# design.net
KiCad netlist of a schematic drawn in Altium Designer
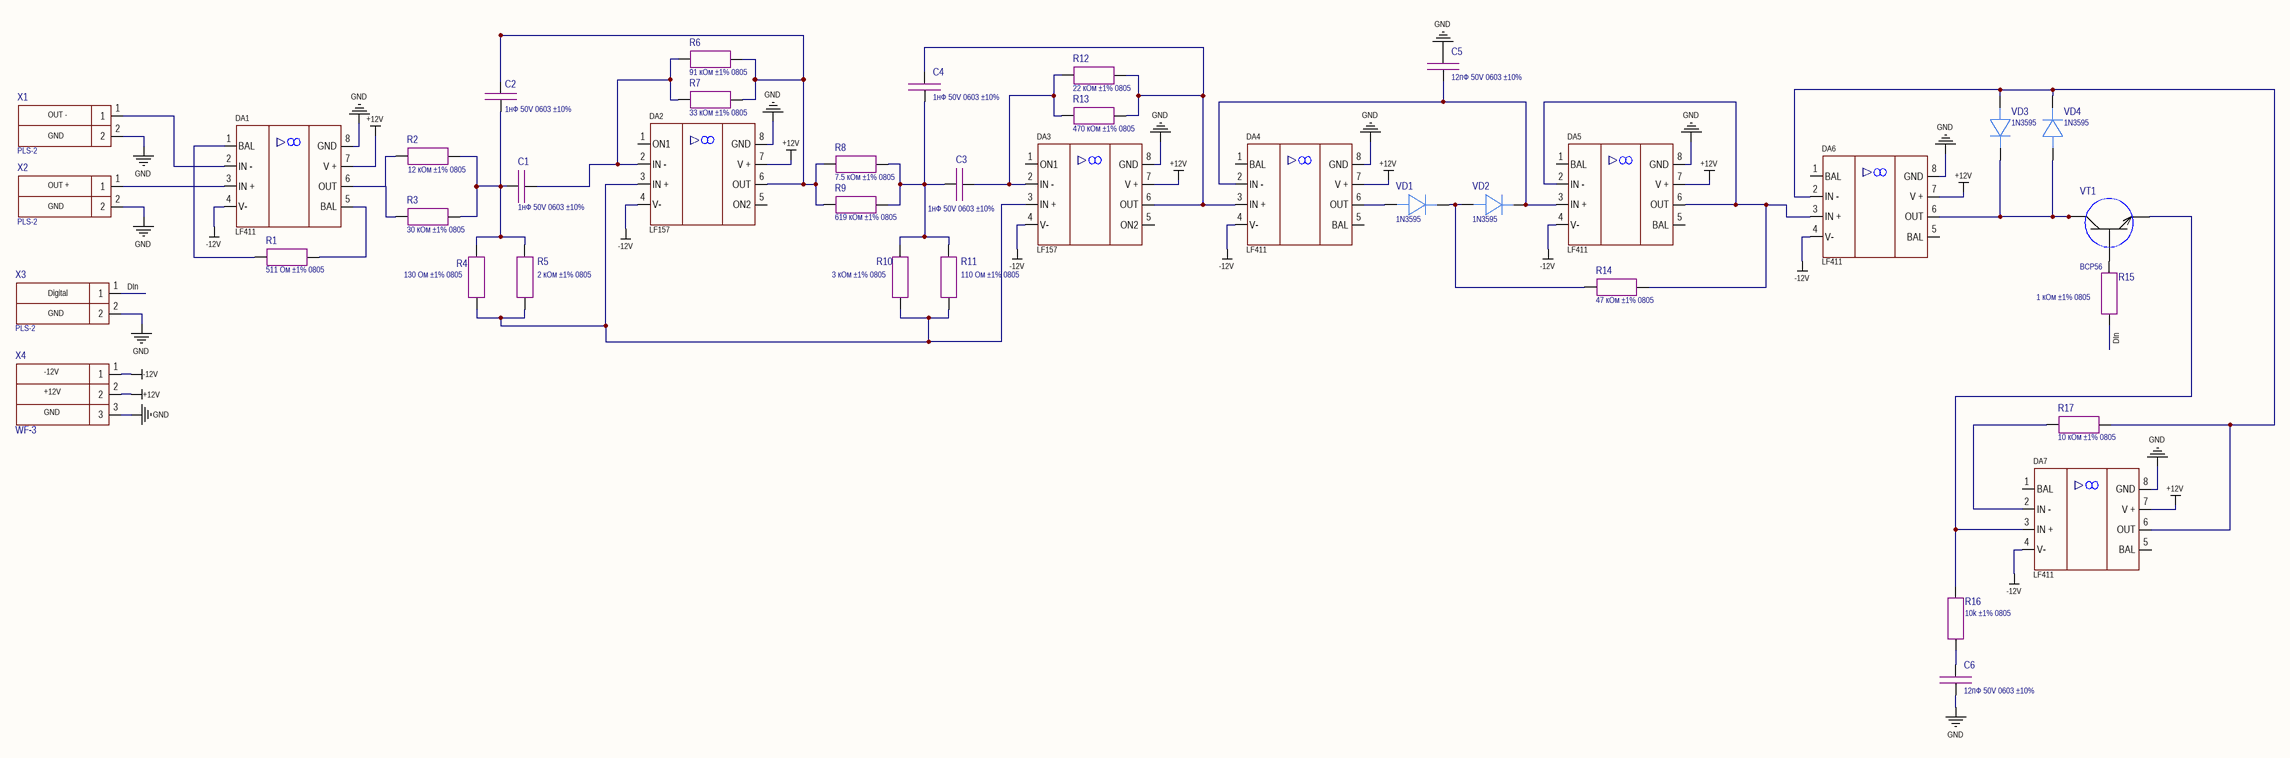
[diagram p0: ДЗ.SchDoc]

(export (version "E")
  (design (tool "Eeschema 10.0.6"))
  (components
    (comp (ref "C1")
      (value "1нФ 50V 0603 ±10%")
      (footprint "CAP: SMD 0603 MD IPC 782")
      (libsource (lib "UOMP capacitors") (part "47p 50V 0603 ±10%"))
    )
    (comp (ref "C2")
      (value "1нФ 50V 0603 ±10%")
      (footprint "CAP: SMD 0603 MD IPC 782")
      (libsource (lib "UOMP capacitors") (part "47p 50V 0603 ±10%"))
    )
    (comp (ref "C3")
      (value "1нФ 50V 0603 ±10%")
      (footprint "CAP: SMD 0603 MD IPC 782")
      (libsource (lib "UOMP capacitors") (part "47p 50V 0603 ±10%"))
    )
    (comp (ref "C4")
      (value "1нФ 50V 0603 ±10%")
      (footprint "CAP: SMD 0603 MD IPC 782")
      (libsource (lib "UOMP capacitors") (part "47p 50V 0603 ±10%"))
    )
    (comp (ref "C5")
      (value "12пФ 50V 0603 ±10%")
      (footprint "CAP: SMD 0603 MD IPC 782")
      (libsource (lib "UOMP capacitors") (part "47p 50V 0603 ±10%"))
    )
    (comp (ref "C6")
      (value "12пФ 50V 0603 ±10%")
      (footprint "CAP: SMD 0603 MD IPC 782")
      (libsource (lib "UOMP capacitors") (part "47p 50V 0603 ±10%"))
    )
    (comp (ref "DA1") (value "LF411") (footprint "IC: PDIP-8") (libsource (lib "") (part "LF411_1")))
    (comp (ref "DA2")
      (value "LF157")
      (footprint "IC: SOIC 8")
      (libsource (lib "UOMP operational amplifier") (part "LF157"))
    )
    (comp (ref "DA3")
      (value "LF157")
      (footprint "IC: SOIC 8")
      (libsource (lib "UOMP operational amplifier") (part "LF157"))
    )
    (comp (ref "DA4") (value "LF411") (footprint "IC: PDIP-8") (libsource (lib "") (part "LF411_1")))
    (comp (ref "DA5")
      (value "LF411")
      (footprint "IC: PDIP-8")
      (libsource (lib "UOMP operational amplifier") (part "LF411"))
    )
    (comp (ref "DA6")
      (value "LF411")
      (footprint "IC: PDIP-8")
      (libsource (lib "UOMP operational amplifier") (part "LF411"))
    )
    (comp (ref "DA7") (value "LF411") (footprint "IC: PDIP-8") (libsource (lib "") (part "LF411_1")))
    (comp (ref "R1")
      (value "511 Ом ±1% 0805")
      (footprint "RES: SMD 0805 MD IPC 782")
      (libsource (lib "UOMP resistors") (part "510 ±1% 0805"))
    )
    (comp (ref "R2")
      (value "12 кОм ±1% 0805")
      (footprint "RES: SMD 0805 MD IPC 782")
      (libsource (lib "UOMP resistors") (part "15k ±1% 0805"))
    )
    (comp (ref "R3")
      (value "30 кОм ±1% 0805")
      (footprint "RES: SMD 0805 MD IPC 782")
      (libsource (lib "UOMP resistors") (part "20k ±1% 0805"))
    )
    (comp (ref "R4")
      (value "130 Ом ±1% 0805")
      (footprint "RES: SMD 0805 MD IPC 782")
      (libsource (lib "UOMP resistors") (part "100k ±1% 0805"))
    )
    (comp (ref "R5")
      (value "2 кОм ±1% 0805")
      (footprint "RES: SMD 0805 MD IPC 782")
      (libsource (lib "UOMP resistors") (part "100k ±1% 0805"))
    )
    (comp (ref "R6")
      (value "91 кОм ±1% 0805")
      (footprint "RES: SMD 0805 MD IPC 782")
      (libsource (lib "UOMP resistors") (part "2k ±1% 0805"))
    )
    (comp (ref "R7")
      (value "33 кОм ±1% 0805")
      (footprint "RES: SMD 0805 MD IPC 782")
      (libsource (lib "UOMP resistors") (part "2k ±1% 0805"))
    )
    (comp (ref "R8")
      (value "7.5 кОм ±1% 0805")
      (footprint "RES: SMD 0805 MD IPC 782")
      (libsource (lib "UOMP resistors") (part "2k ±1% 0805"))
    )
    (comp (ref "R9")
      (value "619 кОм ±1% 0805")
      (footprint "RES: SMD 0805 MD IPC 782")
      (libsource (lib "UOMP resistors") (part "2k ±1% 0805"))
    )
    (comp (ref "R10")
      (value "3 кОм ±1% 0805")
      (footprint "RES: SMD 0805 MD IPC 782")
      (libsource (lib "UOMP resistors") (part "100k ±1% 0805"))
    )
    (comp (ref "R11")
      (value "110 Ом ±1% 0805")
      (footprint "RES: SMD 0805 MD IPC 782")
      (libsource (lib "UOMP resistors") (part "100k ±1% 0805"))
    )
    (comp (ref "R12")
      (value "22 кОм ±1% 0805")
      (footprint "RES: SMD 0805 MD IPC 782")
      (libsource (lib "UOMP resistors") (part "2k ±1% 0805"))
    )
    (comp (ref "R13")
      (value "470 кОм ±1% 0805")
      (footprint "RES: SMD 0805 MD IPC 782")
      (libsource (lib "UOMP resistors") (part "2k ±1% 0805"))
    )
    (comp (ref "R14")
      (value "47 кОм ±1% 0805")
      (footprint "RES: SMD 0805 MD IPC 782")
      (libsource (lib "UOMP resistors") (part "2k ±1% 0805"))
    )
    (comp (ref "R15")
      (value "1 кОм ±1% 0805")
      (footprint "RES: SMD 0805 MD IPC 782")
      (libsource (lib "UOMP resistors") (part "2k ±1% 0805"))
    )
    (comp (ref "R16")
      (value "10k ±1% 0805")
      (footprint "RES: SMD 0805 MD IPC 782")
      (libsource (lib "UOMP resistors") (part "10k ±1% 0805"))
    )
    (comp (ref "R17")
      (value "10 кОм ±1% 0805")
      (footprint "RES: SMD 0805 MD IPC 782")
      (libsource (lib "UOMP resistors") (part "2k ±1% 0805"))
    )
    (comp (ref "VD1")
      (value "1N3595")
      (footprint "DIODE: SMB")
      (libsource (lib "UOMP diode") (part "Rectifier 1A 40V"))
    )
    (comp (ref "VD2")
      (value "1N3595")
      (footprint "DIODE: SMB")
      (libsource (lib "UOMP diode") (part "Rectifier 1A 40V"))
    )
    (comp (ref "VD3")
      (value "1N3595")
      (footprint "DIODE: SMB")
      (libsource (lib "UOMP diode") (part "Rectifier 1A 40V"))
    )
    (comp (ref "VD4")
      (value "1N3595")
      (footprint "DIODE: SMB")
      (libsource (lib "UOMP diode") (part "Rectifier 1A 40V"))
    )
    (comp (ref "VT1")
      (value "BCP56")
      (footprint "IC: SOT 223")
      (libsource (lib "UOMP transistors") (part "BJT NPN BCP56"))
    )
    (comp (ref "X1")
      (value "PLS-2")
      (footprint "CON: 2PIN PLS 2")
      (libsource (lib "UOMP connectors") (part "2 pin PLS 2"))
    )
    (comp (ref "X2")
      (value "PLS-2")
      (footprint "CON: 2PIN PLS 2")
      (libsource (lib "UOMP connectors") (part "2 pin PLS 2"))
    )
    (comp (ref "X3")
      (value "PLS-2")
      (footprint "CON: 2PIN PLS 2")
      (libsource (lib "UOMP connectors") (part "2 pin PLS 2"))
    )
    (comp (ref "X4")
      (value "WF-3")
      (footprint "CON: 3pin wf-3")
      (libsource (lib "UOMP connectors") (part "3 pin WF-3"))
    )
  )
  (nets
    (net (code "1") (name "+12V") (class "Default")
      (node (ref "DA1") (pin "7") (pinfunction "V_+_7") (pintype "passive"))
      (node (ref "DA2") (pin "7") (pinfunction "V_+_7") (pintype "passive"))
      (node (ref "DA3") (pin "7") (pinfunction "V_+_7") (pintype "passive"))
      (node (ref "DA4") (pin "7") (pinfunction "V_+_7") (pintype "passive"))
      (node (ref "DA5") (pin "7") (pinfunction "V_+_7") (pintype "passive"))
      (node (ref "DA6") (pin "7") (pinfunction "V_+_7") (pintype "passive"))
      (node (ref "DA7") (pin "7") (pinfunction "V_+_7") (pintype "passive"))
      (node (ref "X4") (pin "2") (pinfunction "2_2") (pintype "passive"))
    )
    (net (code "2") (name "-12V") (class "Default")
      (node (ref "DA1") (pin "4") (pinfunction "V-_4") (pintype "passive"))
      (node (ref "DA2") (pin "4") (pinfunction "V-_4") (pintype "passive"))
      (node (ref "DA3") (pin "4") (pinfunction "V-_4") (pintype "passive"))
      (node (ref "DA4") (pin "4") (pinfunction "V-_4") (pintype "passive"))
      (node (ref "DA5") (pin "4") (pinfunction "V-_4") (pintype "passive"))
      (node (ref "DA6") (pin "4") (pinfunction "V-_4") (pintype "passive"))
      (node (ref "DA7") (pin "4") (pinfunction "V-_4") (pintype "passive"))
      (node (ref "X4") (pin "1") (pinfunction "1_1") (pintype "passive"))
    )
    (net (code "3") (name "/DIn") (class "Default")
      (node (ref "R15") (pin "2") (pinfunction "2_2") (pintype "passive"))
      (node (ref "X3") (pin "1") (pinfunction "1_1") (pintype "passive"))
    )
    (net (code "4") (name "GND") (class "Default")
      (node (ref "C5") (pin "2") (pinfunction "2_2") (pintype "passive"))
      (node (ref "C6") (pin "1") (pinfunction "1_1") (pintype "passive"))
      (node (ref "DA1") (pin "8") (pinfunction "GND_8") (pintype "passive"))
      (node (ref "DA2") (pin "8") (pinfunction "GND_8") (pintype "passive"))
      (node (ref "DA3") (pin "8") (pinfunction "GND_8") (pintype "passive"))
      (node (ref "DA4") (pin "8") (pinfunction "GND_8") (pintype "passive"))
      (node (ref "DA5") (pin "8") (pinfunction "GND_8") (pintype "passive"))
      (node (ref "DA6") (pin "8") (pinfunction "GND_8") (pintype "passive"))
      (node (ref "DA7") (pin "8") (pinfunction "GND_8") (pintype "passive"))
      (node (ref "X1") (pin "2") (pinfunction "2_2") (pintype "passive"))
      (node (ref "X2") (pin "2") (pinfunction "2_2") (pintype "passive"))
      (node (ref "X3") (pin "2") (pinfunction "2_2") (pintype "passive"))
      (node (ref "X4") (pin "3") (pinfunction "3_3") (pintype "passive"))
    )
    (net (code "5") (name "Net-(C1-Pad2)") (class "Default")
      (node (ref "C1") (pin "2") (pinfunction "2_2") (pintype "passive"))
      (node (ref "C2") (pin "2") (pinfunction "2_2") (pintype "passive"))
      (node (ref "R2") (pin "2") (pinfunction "2_2") (pintype "passive"))
      (node (ref "R3") (pin "2") (pinfunction "2_2") (pintype "passive"))
      (node (ref "R4") (pin "2") (pinfunction "2_2") (pintype "passive"))
      (node (ref "R5") (pin "2") (pinfunction "2_2") (pintype "passive"))
    )
    (net (code "6") (name "Net-(C3-Pad2)") (class "Default")
      (node (ref "C3") (pin "2") (pinfunction "2_2") (pintype "passive"))
      (node (ref "C4") (pin "1") (pinfunction "1_1") (pintype "passive"))
      (node (ref "R10") (pin "2") (pinfunction "2_2") (pintype "passive"))
      (node (ref "R11") (pin "2") (pinfunction "2_2") (pintype "passive"))
      (node (ref "R8") (pin "2") (pinfunction "2_2") (pintype "passive"))
      (node (ref "R9") (pin "2") (pinfunction "2_2") (pintype "passive"))
    )
    (net (code "7") (name "Net-(C6-Pad2)") (class "Default")
      (node (ref "C6") (pin "2") (pinfunction "2_2") (pintype "passive"))
      (node (ref "R16") (pin "2") (pinfunction "2_2") (pintype "passive"))
    )
    (net (code "8") (name "Net-(DA1-BAL-Pad1)") (class "Default")
      (node (ref "DA1") (pin "1") (pinfunction "BAL_1") (pintype "passive"))
      (node (ref "R1") (pin "1") (pinfunction "1_1") (pintype "passive"))
    )
    (net (code "9") (name "Net-(DA1-BAL-Pad5)") (class "Default")
      (node (ref "DA1") (pin "5") (pinfunction "BAL_5") (pintype "passive"))
      (node (ref "R1") (pin "2") (pinfunction "2_2") (pintype "passive"))
    )
    (net (code "10") (name "Net-(DA1-IN_+)") (class "Default")
      (node (ref "DA1") (pin "3") (pinfunction "IN_+_3") (pintype "passive"))
      (node (ref "X2") (pin "1") (pinfunction "1_1") (pintype "passive"))
    )
    (net (code "11") (name "Net-(DA1-IN_-)") (class "Default")
      (node (ref "DA1") (pin "2") (pinfunction "IN_-_2") (pintype "passive"))
      (node (ref "X1") (pin "1") (pinfunction "1_1") (pintype "passive"))
    )
    (net (code "12") (name "Net-(DA1-OUT)") (class "Default")
      (node (ref "DA1") (pin "6") (pinfunction "OUT_6") (pintype "passive"))
      (node (ref "R2") (pin "1") (pinfunction "1_1") (pintype "passive"))
      (node (ref "R3") (pin "1") (pinfunction "1_1") (pintype "passive"))
    )
    (net (code "13") (name "Net-(DA2-IN_+)") (class "Default")
      (node (ref "DA2") (pin "3") (pinfunction "IN_+_3") (pintype "passive"))
      (node (ref "DA3") (pin "3") (pinfunction "IN_+_3") (pintype "passive"))
      (node (ref "R10") (pin "1") (pinfunction "1_1") (pintype "passive"))
      (node (ref "R11") (pin "1") (pinfunction "1_1") (pintype "passive"))
      (node (ref "R4") (pin "1") (pinfunction "1_1") (pintype "passive"))
      (node (ref "R5") (pin "1") (pinfunction "1_1") (pintype "passive"))
    )
    (net (code "14") (name "Net-(DA2-IN_-)") (class "Default")
      (node (ref "C1") (pin "1") (pinfunction "1_1") (pintype "passive"))
      (node (ref "DA2") (pin "2") (pinfunction "IN_-_2") (pintype "passive"))
      (node (ref "R6") (pin "1") (pinfunction "1_1") (pintype "passive"))
      (node (ref "R7") (pin "1") (pinfunction "1_1") (pintype "passive"))
    )
    (net (code "15") (name "Net-(DA2-OUT)") (class "Default")
      (node (ref "C2") (pin "1") (pinfunction "1_1") (pintype "passive"))
      (node (ref "DA2") (pin "6") (pinfunction "OUT_6") (pintype "passive"))
      (node (ref "R6") (pin "2") (pinfunction "2_2") (pintype "passive"))
      (node (ref "R7") (pin "2") (pinfunction "2_2") (pintype "passive"))
      (node (ref "R8") (pin "1") (pinfunction "1_1") (pintype "passive"))
      (node (ref "R9") (pin "1") (pinfunction "1_1") (pintype "passive"))
    )
    (net (code "16") (name "Net-(DA3-IN_-)") (class "Default")
      (node (ref "C3") (pin "1") (pinfunction "1_1") (pintype "passive"))
      (node (ref "DA3") (pin "2") (pinfunction "IN_-_2") (pintype "passive"))
      (node (ref "R12") (pin "1") (pinfunction "1_1") (pintype "passive"))
      (node (ref "R13") (pin "1") (pinfunction "1_1") (pintype "passive"))
    )
    (net (code "17") (name "Net-(DA3-OUT)") (class "Default")
      (node (ref "C4") (pin "2") (pinfunction "2_2") (pintype "passive"))
      (node (ref "DA3") (pin "6") (pinfunction "OUT_6") (pintype "passive"))
      (node (ref "DA4") (pin "3") (pinfunction "IN_+_3") (pintype "passive"))
      (node (ref "R12") (pin "2") (pinfunction "2_2") (pintype "passive"))
      (node (ref "R13") (pin "2") (pinfunction "2_2") (pintype "passive"))
    )
    (net (code "18") (name "Net-(DA4-IN_-)") (class "Default")
      (node (ref "C5") (pin "1") (pinfunction "1_1") (pintype "passive"))
      (node (ref "DA4") (pin "2") (pinfunction "IN_-_2") (pintype "passive"))
      (node (ref "DA5") (pin "3") (pinfunction "IN_+_3") (pintype "passive"))
      (node (ref "VD2") (pin "1") (pinfunction "1_1") (pintype "passive"))
    )
    (net (code "19") (name "Net-(DA4-OUT)") (class "Default")
      (node (ref "DA4") (pin "6") (pinfunction "OUT_6") (pintype "passive"))
      (node (ref "VD1") (pin "2") (pinfunction "2_2") (pintype "passive"))
    )
    (net (code "20") (name "Net-(DA5-IN_-)") (class "Default")
      (node (ref "DA5") (pin "2") (pinfunction "IN_-_2") (pintype "passive"))
      (node (ref "DA5") (pin "6") (pinfunction "OUT_6") (pintype "passive"))
      (node (ref "DA6") (pin "3") (pinfunction "IN_+_3") (pintype "passive"))
      (node (ref "R14") (pin "2") (pinfunction "2_2") (pintype "passive"))
    )
    (net (code "21") (name "Net-(DA6-IN_-)") (class "Default")
      (node (ref "DA6") (pin "2") (pinfunction "IN_-_2") (pintype "passive"))
      (node (ref "DA7") (pin "6") (pinfunction "OUT_6") (pintype "passive"))
      (node (ref "R17") (pin "2") (pinfunction "2_2") (pintype "passive"))
      (node (ref "VD3") (pin "2") (pinfunction "2_2") (pintype "passive"))
      (node (ref "VD4") (pin "1") (pinfunction "1_1") (pintype "passive"))
    )
    (net (code "22") (name "Net-(DA6-OUT)") (class "Default")
      (node (ref "DA6") (pin "6") (pinfunction "OUT_6") (pintype "passive"))
      (node (ref "VD3") (pin "1") (pinfunction "1_1") (pintype "passive"))
      (node (ref "VD4") (pin "2") (pinfunction "2_2") (pintype "passive"))
      (node (ref "VT1") (pin "2") (pinfunction "2_2") (pintype "passive"))
      (node (ref "VT1") (pin "4") (pinfunction "4_4") (pintype "passive"))
    )
    (net (code "23") (name "Net-(DA7-IN_+)") (class "Default")
      (node (ref "DA7") (pin "3") (pinfunction "IN_+_3") (pintype "passive"))
      (node (ref "R16") (pin "1") (pinfunction "1_1") (pintype "passive"))
      (node (ref "VT1") (pin "3") (pinfunction "3_3") (pintype "passive"))
    )
    (net (code "24") (name "Net-(DA7-IN_-)") (class "Default")
      (node (ref "DA7") (pin "2") (pinfunction "IN_-_2") (pintype "passive"))
      (node (ref "R17") (pin "1") (pinfunction "1_1") (pintype "passive"))
    )
    (net (code "25") (name "Net-(R14-Pad1)") (class "Default")
      (node (ref "R14") (pin "1") (pinfunction "1_1") (pintype "passive"))
      (node (ref "VD1") (pin "1") (pinfunction "1_1") (pintype "passive"))
      (node (ref "VD2") (pin "2") (pinfunction "2_2") (pintype "passive"))
    )
    (net (code "26") (name "Net-(R15-Pad1)") (class "Default")
      (node (ref "R15") (pin "1") (pinfunction "1_1") (pintype "passive"))
      (node (ref "VT1") (pin "1") (pinfunction "1_1") (pintype "passive"))
    )
    (net (code "27") (name "unconnected-(DA2-ON1-Pad1)") (class "Default")
      (node (ref "DA2") (pin "1") (pinfunction "ON1_1") (pintype "passive"))
    )
    (net (code "28") (name "unconnected-(DA2-ON2-Pad5)") (class "Default")
      (node (ref "DA2") (pin "5") (pinfunction "ON2_5") (pintype "passive"))
    )
    (net (code "29") (name "unconnected-(DA3-ON1-Pad1)") (class "Default")
      (node (ref "DA3") (pin "1") (pinfunction "ON1_1") (pintype "passive"))
    )
    (net (code "30") (name "unconnected-(DA3-ON2-Pad5)") (class "Default")
      (node (ref "DA3") (pin "5") (pinfunction "ON2_5") (pintype "passive"))
    )
    (net (code "31") (name "unconnected-(DA4-BAL-Pad1)") (class "Default")
      (node (ref "DA4") (pin "1") (pinfunction "BAL_1") (pintype "passive"))
    )
    (net (code "32") (name "unconnected-(DA4-BAL-Pad5)") (class "Default")
      (node (ref "DA4") (pin "5") (pinfunction "BAL_5") (pintype "passive"))
    )
    (net (code "33") (name "unconnected-(DA5-BAL-Pad1)") (class "Default")
      (node (ref "DA5") (pin "1") (pinfunction "BAL_1") (pintype "passive"))
    )
    (net (code "34") (name "unconnected-(DA5-BAL-Pad5)") (class "Default")
      (node (ref "DA5") (pin "5") (pinfunction "BAL_5") (pintype "passive"))
    )
    (net (code "35") (name "unconnected-(DA6-BAL-Pad1)") (class "Default")
      (node (ref "DA6") (pin "1") (pinfunction "BAL_1") (pintype "passive"))
    )
    (net (code "36") (name "unconnected-(DA6-BAL-Pad5)") (class "Default")
      (node (ref "DA6") (pin "5") (pinfunction "BAL_5") (pintype "passive"))
    )
    (net (code "37") (name "unconnected-(DA7-BAL-Pad1)") (class "Default")
      (node (ref "DA7") (pin "1") (pinfunction "BAL_1") (pintype "passive"))
    )
    (net (code "38") (name "unconnected-(DA7-BAL-Pad5)") (class "Default")
      (node (ref "DA7") (pin "5") (pinfunction "BAL_5") (pintype "passive"))
    )
  )
)
